# Dual_H-Bridge.net
KiCad netlist of a schematic drawn in Altium Designer
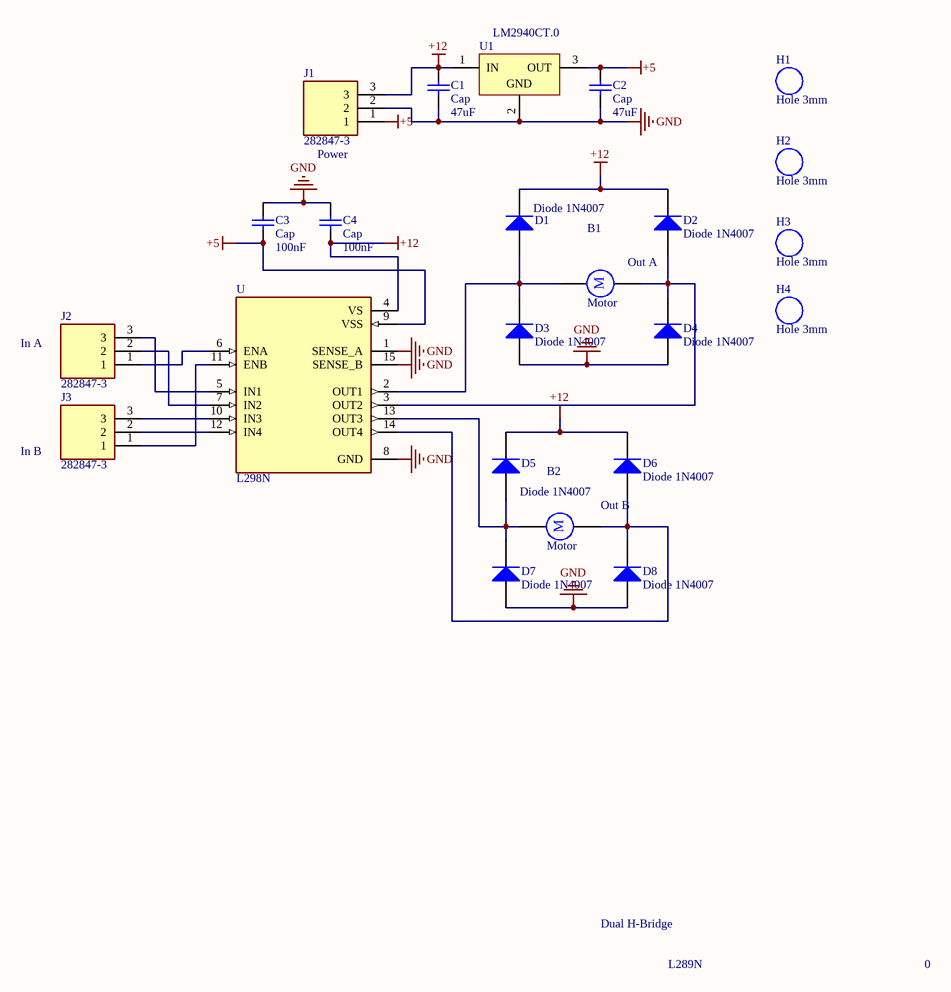
[diagram p0: Dual_H-Bridge.SchDoc]

(export (version "E")
  (design (tool "Eeschema 10.0.6"))
  (components
    (comp (ref "B1")
      (value "Motor")
      (footprint "RB5-10.5")
      (description "Motor, General Kind")
      (fields (field (name "PUBLISHER") "Altium Limited"))
      (libsource (lib "Miscellaneous Devices") (part "Motor"))
    )
    (comp (ref "B2")
      (value "Motor")
      (footprint "RB5-10.5")
      (description "Motor, General Kind")
      (fields (field (name "PUBLISHER") "Altium Limited"))
      (libsource (lib "Miscellaneous Devices") (part "Motor"))
    )
    (comp (ref "C1")
      (value "Cap")
      (footprint "RAD-0.3")
      (description "Capacitor")
      (fields (field (name "ALTIUM_VALUE") "47uF") (field (name "PUBLISHER") "Altium Limited"))
      (libsource (lib "Miscellaneous Devices") (part "Cap"))
    )
    (comp (ref "C2")
      (value "Cap")
      (footprint "RAD-0.3")
      (description "Capacitor")
      (fields (field (name "ALTIUM_VALUE") "47uF") (field (name "PUBLISHER") "Altium Limited"))
      (libsource (lib "Miscellaneous Devices") (part "Cap"))
    )
    (comp (ref "C3")
      (value "Cap")
      (footprint "RAD-0.3")
      (description "Capacitor")
      (fields (field (name "ALTIUM_VALUE") "100nF") (field (name "PUBLISHER") "Altium Limited"))
      (libsource (lib "Miscellaneous Devices") (part "Cap"))
    )
    (comp (ref "C4")
      (value "Cap")
      (footprint "RAD-0.3")
      (description "Capacitor")
      (fields (field (name "ALTIUM_VALUE") "100nF") (field (name "PUBLISHER") "Altium Limited"))
      (libsource (lib "Miscellaneous Devices") (part "Cap"))
    )
    (comp (ref "D1")
      (value "Diode 1N4007")
      (footprint "DO-41")
      (description "1 Amp General Purpose Rectifier")
      (fields (field (name "PUBLISHER") "Altium Limited"))
      (libsource (lib "Miscellaneous Devices") (part "Diode 1N4007"))
    )
    (comp (ref "D2")
      (value "Diode 1N4007")
      (footprint "DO-41")
      (description "1 Amp General Purpose Rectifier")
      (fields (field (name "PUBLISHER") "Altium Limited"))
      (libsource (lib "Miscellaneous Devices") (part "Diode 1N4007"))
    )
    (comp (ref "D3")
      (value "Diode 1N4007")
      (footprint "DO-41")
      (description "1 Amp General Purpose Rectifier")
      (fields (field (name "PUBLISHER") "Altium Limited"))
      (libsource (lib "Miscellaneous Devices") (part "Diode 1N4007"))
    )
    (comp (ref "D4")
      (value "Diode 1N4007")
      (footprint "DO-41")
      (description "1 Amp General Purpose Rectifier")
      (fields (field (name "PUBLISHER") "Altium Limited"))
      (libsource (lib "Miscellaneous Devices") (part "Diode 1N4007"))
    )
    (comp (ref "D5")
      (value "Diode 1N4007")
      (footprint "DO-41")
      (description "1 Amp General Purpose Rectifier")
      (fields (field (name "PUBLISHER") "Altium Limited"))
      (libsource (lib "Miscellaneous Devices") (part "Diode 1N4007"))
    )
    (comp (ref "D6")
      (value "Diode 1N4007")
      (footprint "DO-41")
      (description "1 Amp General Purpose Rectifier")
      (fields (field (name "PUBLISHER") "Altium Limited"))
      (libsource (lib "Miscellaneous Devices") (part "Diode 1N4007"))
    )
    (comp (ref "D7")
      (value "Diode 1N4007")
      (footprint "DO-41")
      (description "1 Amp General Purpose Rectifier")
      (fields (field (name "PUBLISHER") "Altium Limited"))
      (libsource (lib "Miscellaneous Devices") (part "Diode 1N4007"))
    )
    (comp (ref "D8")
      (value "Diode 1N4007")
      (footprint "DO-41")
      (description "1 Amp General Purpose Rectifier")
      (fields (field (name "PUBLISHER") "Altium Limited"))
      (libsource (lib "Miscellaneous Devices") (part "Diode 1N4007"))
    )
    (comp (ref "H1")
      (value "Hole 3mm")
      (footprint "Hole 3mm")
      (libsource (lib "ECE LIB new") (part "Hole 3mm"))
    )
    (comp (ref "H2")
      (value "Hole 3mm")
      (footprint "Hole 3mm")
      (libsource (lib "ECE LIB new") (part "Hole 3mm"))
    )
    (comp (ref "H3")
      (value "Hole 3mm")
      (footprint "Hole 3mm")
      (libsource (lib "ECE LIB new") (part "Hole 3mm"))
    )
    (comp (ref "H4")
      (value "Hole 3mm")
      (footprint "Hole 3mm")
      (libsource (lib "ECE LIB new") (part "Hole 3mm"))
    )
    (comp (ref "J1")
      (value "282847-3")
      (footprint "TE_282847-3")
      (description "Conn Eurostyle Block 3 POS 5.08mm Solder Thru-Hole 17.5A/Contact Automotive Carton")
      (fields (field (name "MF") "TE Connectivity"))
      (libsource (lib "Screw Terminal 3") (part "282847-3"))
    )
    (comp (ref "J2")
      (value "282847-3")
      (footprint "TE_282847-3")
      (description "Conn Eurostyle Block 3 POS 5.08mm Solder Thru-Hole 17.5A/Contact Automotive Carton")
      (fields (field (name "MF") "TE Connectivity"))
      (libsource (lib "Screw Terminal 3") (part "282847-3"))
    )
    (comp (ref "J3")
      (value "282847-3")
      (footprint "TE_282847-3")
      (description "Conn Eurostyle Block 3 POS 5.08mm Solder Thru-Hole 17.5A/Contact Automotive Carton")
      (fields (field (name "MF") "TE Connectivity"))
      (libsource (lib "Screw Terminal 3") (part "282847-3"))
    )
    (comp (ref "U")
      (value "L298N")
      (footprint "TO127P2020X500X2100-15")
      (description "Half Bridge _4_ Driver DC Motors, Relays, Solenoids, Stepper Motors Bipolar 15-Multiwatt")
      (fields (field (name "MF") "STMicroelectronics"))
      (libsource (lib "L298N") (part "L298N"))
    )
    (comp (ref "U1")
      (value "LM2940CT.0")
      (footprint "T03B")
      (description "1A Low Dropout Regulator, 3-pin TO-220")
      (fields
        (field (name "PARTNUMBER") "LM2940CT-5.0")
        (field (name "MANUFACTURER") "National Semiconductor")
      )
      (libsource (lib "ECE LIB new") (part "LM2940CT-5.0_1"))
    )
  )
  (nets
    (net (code "1") (name "+5") (class "Default")
      (node (ref "C2") (pin "2") (pinfunction "2_2") (pintype "passive"))
      (node (ref "C3") (pin "1") (pinfunction "1_1") (pintype "passive"))
      (node (ref "J1") (pin "1") (pinfunction "1_1") (pintype "passive"))
      (node (ref "U") (pin "9") (pinfunction "VSS_9") (pintype "input"))
      (node (ref "U1") (pin "3") (pinfunction "OUT_3") (pintype "power_in"))
    )
    (net (code "2") (name "+12") (class "Default")
      (node (ref "C1") (pin "1") (pinfunction "1_1") (pintype "passive"))
      (node (ref "C4") (pin "2") (pinfunction "2_2") (pintype "passive"))
      (node (ref "D1") (pin "2") (pinfunction "K_2") (pintype "passive"))
      (node (ref "D2") (pin "2") (pinfunction "K_2") (pintype "passive"))
      (node (ref "D5") (pin "2") (pinfunction "K_2") (pintype "passive"))
      (node (ref "D6") (pin "2") (pinfunction "K_2") (pintype "passive"))
      (node (ref "J1") (pin "3") (pinfunction "3_3") (pintype "passive"))
      (node (ref "U") (pin "4") (pinfunction "VS_4") (pintype "power_in"))
      (node (ref "U1") (pin "1") (pinfunction "IN_1") (pintype "power_in"))
    )
    (net (code "3") (name "GND") (class "Default")
      (node (ref "C1") (pin "2") (pinfunction "2_2") (pintype "passive"))
      (node (ref "C2") (pin "1") (pinfunction "1_1") (pintype "passive"))
      (node (ref "C3") (pin "2") (pinfunction "2_2") (pintype "passive"))
      (node (ref "C4") (pin "1") (pinfunction "1_1") (pintype "passive"))
      (node (ref "D3") (pin "1") (pinfunction "A_1") (pintype "passive"))
      (node (ref "D4") (pin "1") (pinfunction "A_1") (pintype "passive"))
      (node (ref "D7") (pin "1") (pinfunction "A_1") (pintype "passive"))
      (node (ref "D8") (pin "1") (pinfunction "A_1") (pintype "passive"))
      (node (ref "J1") (pin "2") (pinfunction "2_2") (pintype "passive"))
      (node (ref "U") (pin "1") (pinfunction "SENSE_A_1") (pintype "passive"))
      (node (ref "U") (pin "15") (pinfunction "SENSE_B_15") (pintype "passive"))
      (node (ref "U") (pin "8") (pinfunction "GND_8") (pintype "power_in"))
      (node (ref "U1") (pin "2") (pinfunction "GND_2") (pintype "power_in"))
    )
    (net (code "4") (name "Net-(D1-A)") (class "Default")
      (node (ref "B1") (pin "1") (pinfunction "1_1") (pintype "passive"))
      (node (ref "D1") (pin "1") (pinfunction "A_1") (pintype "passive"))
      (node (ref "D3") (pin "2") (pinfunction "K_2") (pintype "passive"))
      (node (ref "U") (pin "2") (pinfunction "OUT1_2") (pintype "output"))
    )
    (net (code "5") (name "Net-(D2-A)") (class "Default")
      (node (ref "B1") (pin "2") (pinfunction "2_2") (pintype "passive"))
      (node (ref "D2") (pin "1") (pinfunction "A_1") (pintype "passive"))
      (node (ref "D4") (pin "2") (pinfunction "K_2") (pintype "passive"))
      (node (ref "U") (pin "3") (pinfunction "OUT2_3") (pintype "output"))
    )
    (net (code "6") (name "Net-(D5-A)") (class "Default")
      (node (ref "B2") (pin "1") (pinfunction "1_1") (pintype "passive"))
      (node (ref "D5") (pin "1") (pinfunction "A_1") (pintype "passive"))
      (node (ref "D7") (pin "2") (pinfunction "K_2") (pintype "passive"))
      (node (ref "U") (pin "13") (pinfunction "OUT3_13") (pintype "output"))
    )
    (net (code "7") (name "Net-(D6-A)") (class "Default")
      (node (ref "B2") (pin "2") (pinfunction "2_2") (pintype "passive"))
      (node (ref "D6") (pin "1") (pinfunction "A_1") (pintype "passive"))
      (node (ref "D8") (pin "2") (pinfunction "K_2") (pintype "passive"))
      (node (ref "U") (pin "14") (pinfunction "OUT4_14") (pintype "output"))
    )
    (net (code "8") (name "Net-(U-ENA)") (class "Default")
      (node (ref "J2") (pin "1") (pinfunction "1_1") (pintype "passive"))
      (node (ref "U") (pin "6") (pinfunction "ENA_6") (pintype "input"))
    )
    (net (code "9") (name "Net-(U-ENB)") (class "Default")
      (node (ref "J3") (pin "1") (pinfunction "1_1") (pintype "passive"))
      (node (ref "U") (pin "11") (pinfunction "ENB_11") (pintype "input"))
    )
    (net (code "10") (name "Net-(U-IN1)") (class "Default")
      (node (ref "J2") (pin "3") (pinfunction "3_3") (pintype "passive"))
      (node (ref "U") (pin "5") (pinfunction "IN1_5") (pintype "input"))
    )
    (net (code "11") (name "Net-(U-IN2)") (class "Default")
      (node (ref "J2") (pin "2") (pinfunction "2_2") (pintype "passive"))
      (node (ref "U") (pin "7") (pinfunction "IN2_7") (pintype "input"))
    )
    (net (code "12") (name "Net-(U-IN3)") (class "Default")
      (node (ref "J3") (pin "3") (pinfunction "3_3") (pintype "passive"))
      (node (ref "U") (pin "10") (pinfunction "IN3_10") (pintype "input"))
    )
    (net (code "13") (name "Net-(U-IN4)") (class "Default")
      (node (ref "J3") (pin "2") (pinfunction "2_2") (pintype "passive"))
      (node (ref "U") (pin "12") (pinfunction "IN4_12") (pintype "input"))
    )
  )
)
